# STM32F103-V1_0.net
KiCad netlist of a schematic drawn in Altium Designer
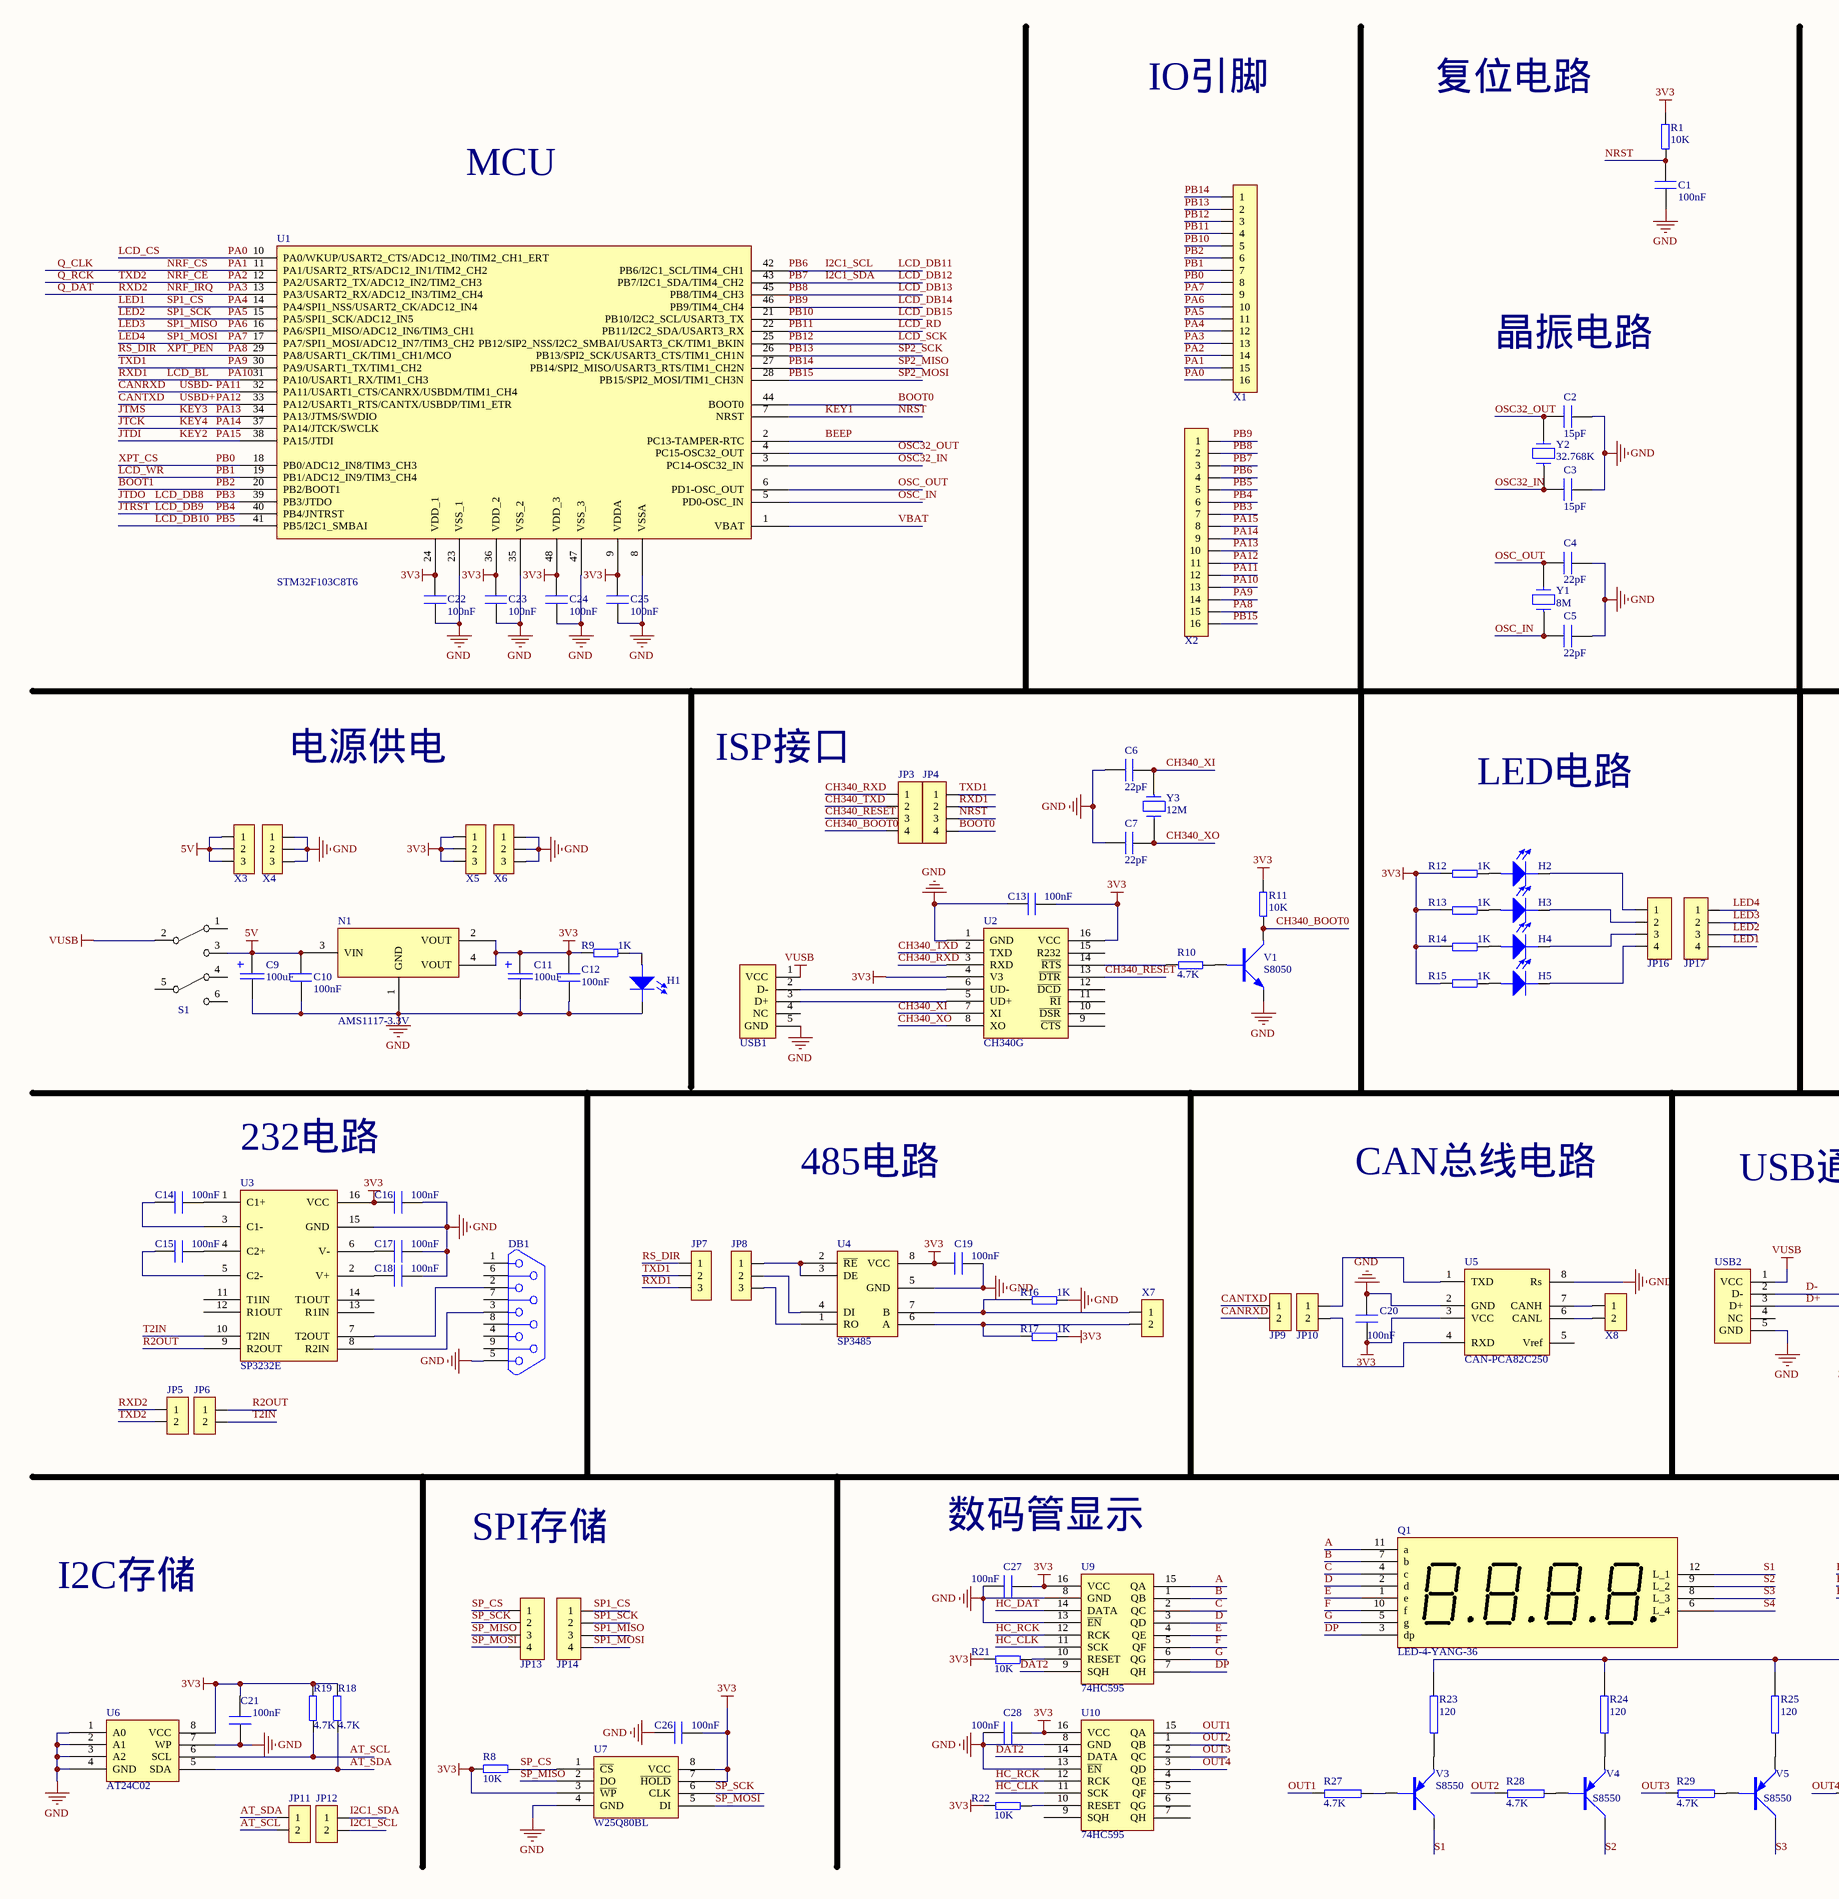
[diagram p0: STM32F103-V1.0.SchDoc, left]
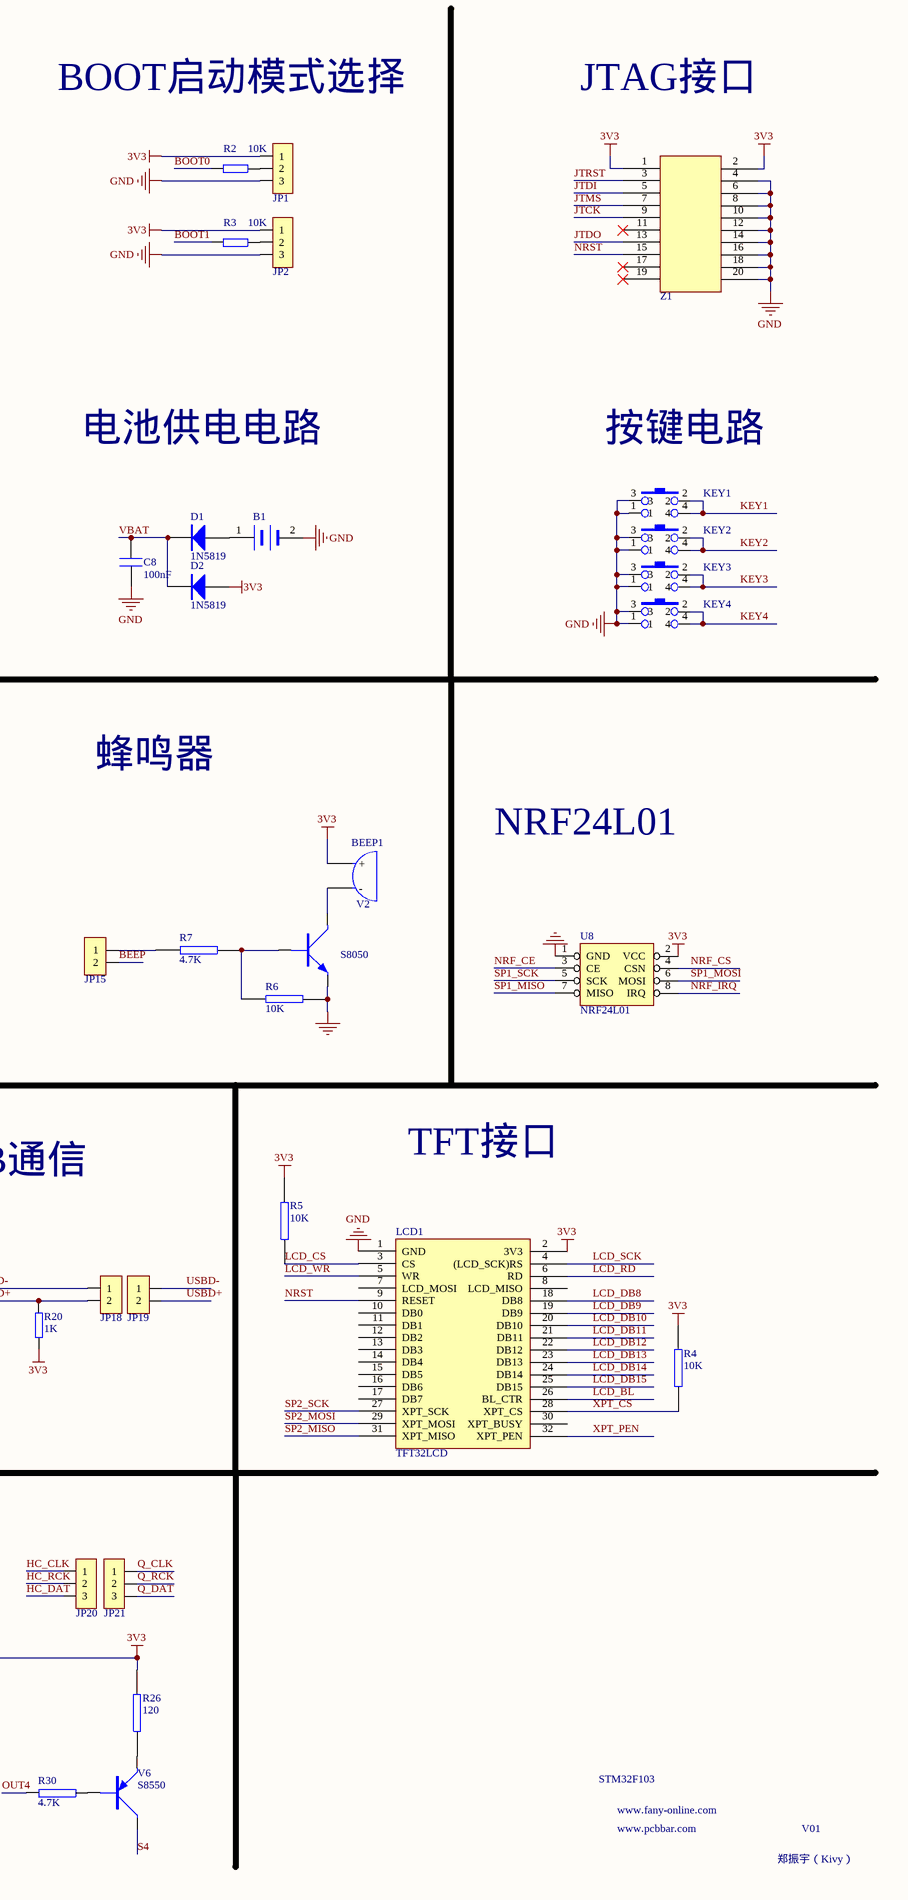
[diagram p1: STM32F103-V1.0.SchDoc, right]

(export (version "E")
  (design (tool "Eeschema 10.0.6"))
  (components
    (comp (ref "B1") (value "BATTERY") (footprint "CR1220") (libsource (lib "Liuzhx") (part "BATTERY")))
    (comp (ref "BEEP1") (value "BEEP") (footprint "SOT12-7.6") (libsource (lib "RationSTM32") (part "BEEP")))
    (comp (ref "C1")
      (value "100nF")
      (footprint "C0805")
      (description "Capacitor")
      (libsource (lib "Liuzhx") (part "普通贴片电容"))
    )
    (comp (ref "C2")
      (value "15pF")
      (footprint "C0805")
      (description "Capacitor")
      (libsource (lib "Liuzhx") (part "普通贴片电容"))
    )
    (comp (ref "C3")
      (value "15pF")
      (footprint "C0805")
      (description "Capacitor")
      (libsource (lib "Liuzhx") (part "普通贴片电容"))
    )
    (comp (ref "C4")
      (value "22pF")
      (footprint "C0805")
      (description "Capacitor")
      (libsource (lib "Liuzhx") (part "普通贴片电容"))
    )
    (comp (ref "C5")
      (value "22pF")
      (footprint "C0805")
      (description "Capacitor")
      (libsource (lib "Liuzhx") (part "普通贴片电容"))
    )
    (comp (ref "C6")
      (value "22pF")
      (footprint "C0805")
      (description "Capacitor")
      (libsource (lib "Liuzhx") (part "普通贴片电容"))
    )
    (comp (ref "C7")
      (value "22pF")
      (footprint "C0805")
      (description "Capacitor")
      (libsource (lib "Liuzhx") (part "普通贴片电容"))
    )
    (comp (ref "C8")
      (value "100nF")
      (footprint "C0805")
      (description "Capacitor")
      (libsource (lib "Liuzhx") (part "普通贴片电容"))
    )
    (comp (ref "C9") (value "100uF") (footprint "CAP5*5_4") (libsource (lib "Liuzhx") (part "极性电容器")))
    (comp (ref "C10")
      (value "100nF")
      (footprint "C0805")
      (description "Capacitor")
      (libsource (lib "Liuzhx") (part "普通贴片电容"))
    )
    (comp (ref "C11") (value "100uF") (footprint "CAP5*5_4") (libsource (lib "Liuzhx") (part "极性电容器")))
    (comp (ref "C12")
      (value "100nF")
      (footprint "C0805")
      (description "Capacitor")
      (libsource (lib "Liuzhx") (part "普通贴片电容"))
    )
    (comp (ref "C13")
      (value "100nF")
      (footprint "C0805")
      (description "Capacitor")
      (libsource (lib "Liuzhx") (part "普通贴片电容"))
    )
    (comp (ref "C14")
      (value "100nF")
      (footprint "C0805")
      (description "Capacitor")
      (libsource (lib "Liuzhx") (part "普通贴片电容"))
    )
    (comp (ref "C15")
      (value "100nF")
      (footprint "C0805")
      (description "Capacitor")
      (libsource (lib "Liuzhx") (part "普通贴片电容"))
    )
    (comp (ref "C16")
      (value "100nF")
      (footprint "C0805")
      (description "Capacitor")
      (libsource (lib "Liuzhx") (part "普通贴片电容"))
    )
    (comp (ref "C17")
      (value "100nF")
      (footprint "C0805")
      (description "Capacitor")
      (libsource (lib "Liuzhx") (part "普通贴片电容"))
    )
    (comp (ref "C18")
      (value "100nF")
      (footprint "C0805")
      (description "Capacitor")
      (libsource (lib "Liuzhx") (part "普通贴片电容"))
    )
    (comp (ref "C19")
      (value "100nF")
      (footprint "C0805")
      (description "Capacitor")
      (libsource (lib "Liuzhx") (part "普通贴片电容"))
    )
    (comp (ref "C20")
      (value "100nF")
      (footprint "C0805")
      (description "Capacitor")
      (libsource (lib "GKSSCH") (part "普通贴片电容"))
    )
    (comp (ref "C21")
      (value "100nF")
      (footprint "C0805")
      (description "Capacitor")
      (libsource (lib "Liuzhx") (part "普通贴片电容"))
    )
    (comp (ref "C22")
      (value "100nF")
      (footprint "C0805")
      (description "Capacitor")
      (libsource (lib "Liuzhx") (part "普通贴片电容"))
    )
    (comp (ref "C23")
      (value "100nF")
      (footprint "C0805")
      (description "Capacitor")
      (libsource (lib "Liuzhx") (part "普通贴片电容"))
    )
    (comp (ref "C24")
      (value "100nF")
      (footprint "C0805")
      (description "Capacitor")
      (libsource (lib "Liuzhx") (part "普通贴片电容"))
    )
    (comp (ref "C25")
      (value "100nF")
      (footprint "C0805")
      (description "Capacitor")
      (libsource (lib "Liuzhx") (part "普通贴片电容"))
    )
    (comp (ref "C26")
      (value "100nF")
      (footprint "C0805")
      (description "Capacitor")
      (libsource (lib "Liuzhx") (part "普通贴片电容"))
    )
    (comp (ref "C27")
      (value "100nF")
      (footprint "C0805")
      (description "Capacitor")
      (libsource (lib "Liuzhx") (part "普通贴片电容"))
    )
    (comp (ref "C28")
      (value "100nF")
      (footprint "C0805")
      (description "Capacitor")
      (libsource (lib "Liuzhx") (part "普通贴片电容"))
    )
    (comp (ref "D1")
      (value "1N5819")
      (footprint "1N4148-T")
      (description "Diode 1N series")
      (libsource (lib "Liuzhx") (part "贴片二极管"))
    )
    (comp (ref "D2")
      (value "1N5819")
      (footprint "1N4148-T")
      (description "Diode 1N series")
      (libsource (lib "Liuzhx") (part "贴片二极管"))
    )
    (comp (ref "DB1")
      (value "DB9M")
      (footprint "DB9-M")
      (description "母头")
      (libsource (lib "Liuzhx") (part "DB9M"))
    )
    (comp (ref "H1") (value "发光二极管") (footprint "LED1206") (libsource (lib "Liuzhx") (part "发光二极管")))
    (comp (ref "H2") (value "发光二极管") (footprint "LED1206") (libsource (lib "Liuzhx") (part "发光二极管")))
    (comp (ref "H3") (value "发光二极管") (footprint "LED1206") (libsource (lib "Liuzhx") (part "发光二极管")))
    (comp (ref "H4") (value "发光二极管") (footprint "LED1206") (libsource (lib "Liuzhx") (part "发光二极管")))
    (comp (ref "H5") (value "发光二极管") (footprint "LED1206") (libsource (lib "Liuzhx") (part "发光二极管")))
    (comp (ref "JP1")
      (value "JX3")
      (footprint "SIP3")
      (description "Connector")
      (libsource (lib "") (part "JX3_1"))
    )
    (comp (ref "JP2")
      (value "JX3")
      (footprint "SIP3")
      (description "Connector")
      (libsource (lib "") (part "JX3_1"))
    )
    (comp (ref "JP3")
      (value "JX4")
      (footprint "SIP4")
      (description "Connector")
      (libsource (lib "") (part "JX4_1"))
    )
    (comp (ref "JP4")
      (value "JX4")
      (footprint "SIP4")
      (description "Connector")
      (libsource (lib "Liuzhx") (part "JX4"))
    )
    (comp (ref "JP5")
      (value "JX2")
      (footprint "SIP2")
      (description "Connector")
      (libsource (lib "Liuzhx") (part "JX2"))
    )
    (comp (ref "JP6")
      (value "JX2")
      (footprint "SIP2")
      (description "Connector")
      (libsource (lib "") (part "JX2_1"))
    )
    (comp (ref "JP7")
      (value "JX3")
      (footprint "SIP3")
      (description "Connector")
      (libsource (lib "") (part "JX3_1"))
    )
    (comp (ref "JP8")
      (value "JX3")
      (footprint "SIP3")
      (description "Connector")
      (libsource (lib "Liuzhx") (part "JX3"))
    )
    (comp (ref "JP9")
      (value "JX2")
      (footprint "SIP2")
      (description "Connector")
      (libsource (lib "GKSSCH") (part "JX2"))
    )
    (comp (ref "JP10")
      (value "JX2")
      (footprint "SIP2")
      (description "Connector")
      (libsource (lib "") (part "JX2_1"))
    )
    (comp (ref "JP11")
      (value "JX2")
      (footprint "SIP2")
      (description "Connector")
      (libsource (lib "Liuzhx") (part "JX2"))
    )
    (comp (ref "JP12")
      (value "JX2")
      (footprint "SIP2")
      (description "Connector")
      (libsource (lib "") (part "JX2_1"))
    )
    (comp (ref "JP13")
      (value "JX4")
      (footprint "SIP4")
      (description "Connector")
      (libsource (lib "") (part "JX4_1"))
    )
    (comp (ref "JP14")
      (value "JX4")
      (footprint "SIP4")
      (description "Connector")
      (libsource (lib "Liuzhx") (part "JX4"))
    )
    (comp (ref "JP15")
      (value "JX2")
      (footprint "SIP2")
      (description "Connector")
      (libsource (lib "") (part "JX2_1"))
    )
    (comp (ref "JP16")
      (value "JX4")
      (footprint "SIP4")
      (description "Connector")
      (libsource (lib "") (part "JX4_1"))
    )
    (comp (ref "JP17")
      (value "JX4")
      (footprint "SIP4")
      (description "Connector")
      (libsource (lib "Liuzhx") (part "JX4"))
    )
    (comp (ref "JP18")
      (value "JX2")
      (footprint "SIP2")
      (description "Connector")
      (libsource (lib "Liuzhx") (part "JX2"))
    )
    (comp (ref "JP19")
      (value "JX2")
      (footprint "SIP2")
      (description "Connector")
      (libsource (lib "") (part "JX2_1"))
    )
    (comp (ref "JP20")
      (value "JX3")
      (footprint "SIP3")
      (description "Connector")
      (libsource (lib "") (part "JX3_1"))
    )
    (comp (ref "JP21")
      (value "JX3")
      (footprint "SIP3")
      (description "Connector")
      (libsource (lib "Liuzhx") (part "JX3"))
    )
    (comp (ref "KEY1") (value "SW-66B7") (footprint "SW-66") (libsource (lib "Liuzhx") (part "SW-66B7")))
    (comp (ref "KEY2") (value "SW-66B7") (footprint "SW-66") (libsource (lib "Liuzhx") (part "SW-66B7")))
    (comp (ref "KEY3") (value "SW-66B7") (footprint "SW-66") (libsource (lib "Liuzhx") (part "SW-66B7")))
    (comp (ref "KEY4") (value "SW-66B7") (footprint "SW-66") (libsource (lib "Liuzhx") (part "SW-66B7")))
    (comp (ref "LCD1") (value "TFT32LCD") (footprint "HEAD16×2") (libsource (lib "Liuzhx") (part "TFT32LCD")))
    (comp (ref "N1")
      (value "AMS1117-3.3V")
      (footprint "SOT223")
      (libsource (lib "Liuzhx") (part "AMS1117-3.3V"))
    )
    (comp (ref "Q1")
      (value "LED-4-YANG-36")
      (footprint "LED0.36-4")
      (libsource (lib "Liuzhx") (part "LED-4-YANG-36"))
    )
    (comp (ref "R1") (value "10K") (footprint "R0805") (libsource (lib "Liuzhx") (part "普通贴片电阻")))
    (comp (ref "R2") (value "10K") (footprint "R0805") (libsource (lib "Liuzhx") (part "普通贴片电阻")))
    (comp (ref "R3") (value "10K") (footprint "R0805") (libsource (lib "Liuzhx") (part "普通贴片电阻")))
    (comp (ref "R4") (value "10K") (footprint "R0805") (libsource (lib "RationSTM32") (part "RES")))
    (comp (ref "R5") (value "10K") (footprint "R0805") (libsource (lib "RationSTM32") (part "RES")))
    (comp (ref "R6") (value "10K") (footprint "R0805") (libsource (lib "RationSTM32") (part "RES")))
    (comp (ref "R7") (value "4.7K") (footprint "R0805") (libsource (lib "RationSTM32") (part "RES")))
    (comp (ref "R8") (value "10K") (footprint "R0805") (libsource (lib "Liuzhx") (part "普通贴片电阻")))
    (comp (ref "R9") (value "1K") (footprint "R0805") (libsource (lib "Liuzhx") (part "普通贴片电阻")))
    (comp (ref "R10") (value "4.7K") (footprint "R0805") (libsource (lib "Liuzhx") (part "普通贴片电阻")))
    (comp (ref "R11") (value "10K") (footprint "R0805") (libsource (lib "Liuzhx") (part "普通贴片电阻")))
    (comp (ref "R12") (value "1K") (footprint "R0805") (libsource (lib "Liuzhx") (part "普通贴片电阻")))
    (comp (ref "R13") (value "1K") (footprint "R0805") (libsource (lib "Liuzhx") (part "普通贴片电阻")))
    (comp (ref "R14") (value "1K") (footprint "R0805") (libsource (lib "Liuzhx") (part "普通贴片电阻")))
    (comp (ref "R15") (value "1K") (footprint "R0805") (libsource (lib "Liuzhx") (part "普通贴片电阻")))
    (comp (ref "R16") (value "1K") (footprint "R0805") (libsource (lib "Liuzhx") (part "普通贴片电阻")))
    (comp (ref "R17") (value "1K") (footprint "R0805") (libsource (lib "Liuzhx") (part "普通贴片电阻")))
    (comp (ref "R18") (value "4.7K") (footprint "R0805") (libsource (lib "Liuzhx") (part "普通贴片电阻")))
    (comp (ref "R19") (value "4.7K") (footprint "R0805") (libsource (lib "Liuzhx") (part "普通贴片电阻")))
    (comp (ref "R20") (value "1K") (footprint "R0805") (libsource (lib "Liuzhx") (part "普通贴片电阻")))
    (comp (ref "R21") (value "10K") (footprint "R0805") (libsource (lib "Liuzhx") (part "普通贴片电阻")))
    (comp (ref "R22") (value "10K") (footprint "R0805") (libsource (lib "Liuzhx") (part "普通贴片电阻")))
    (comp (ref "R23") (value "120") (footprint "R0805") (libsource (lib "STM32F103-V1.0") (part "RES")))
    (comp (ref "R24") (value "120") (footprint "R0805") (libsource (lib "STM32F103-V1.0") (part "RES")))
    (comp (ref "R25") (value "120") (footprint "R0805") (libsource (lib "STM32F103-V1.0") (part "RES")))
    (comp (ref "R26") (value "120") (footprint "R0805") (libsource (lib "STM32F103-V1.0") (part "RES")))
    (comp (ref "R27") (value "4.7K") (footprint "R0805") (libsource (lib "STM32F103-V1.0") (part "RES2")))
    (comp (ref "R28") (value "4.7K") (footprint "R0805") (libsource (lib "STM32F103-V1.0") (part "RES2")))
    (comp (ref "R29") (value "4.7K") (footprint "R0805") (libsource (lib "STM32F103-V1.0") (part "RES2")))
    (comp (ref "R30") (value "4.7K") (footprint "R0805") (libsource (lib "STM32F103-V1.0") (part "RES2")))
    (comp (ref "S1") (value "SWITCH-6") (footprint "SW-AJ") (libsource (lib "Liuzhx") (part "SWITCH-6")))
    (comp (ref "U1")
      (value "STM32F103C8T6")
      (footprint "LQFP48")
      (libsource (lib "STM32F103-V1.0") (part "STM32F103C8T6"))
    )
    (comp (ref "U2") (value "CH340G") (footprint "SOIC16") (libsource (lib "Liuzhx") (part "CH340G")))
    (comp (ref "U3")
      (value "SP3232E")
      (footprint "SOIC16")
      (description "SP3232EEN-L/TR;SOIC-39MM")
      (libsource (lib "Liuzhx") (part "SP3232E"))
    )
    (comp (ref "U4") (value "SP3485") (footprint "SO-8") (libsource (lib "Liuzhx") (part "MAX3082")))
    (comp (ref "U5")
      (value "CAN-PCA82C250")
      (footprint "SO-8")
      (libsource (lib "GKSSCH") (part "CAN-PCA82C250"))
    )
    (comp (ref "U6") (value "AT24C02") (footprint "SO-8") (libsource (lib "Liuzhx") (part "AT24C02")))
    (comp (ref "U7") (value "W25Q80BL") (footprint "W25Q-SO8") (libsource (lib "Liuzhx") (part "W25Q80BL")))
    (comp (ref "U8") (value "NRF24L01") (footprint "NRF24L01") (libsource (lib "Liuzhx") (part "NRF24L01")))
    (comp (ref "U9")
      (value "74HC595")
      (footprint "SO-16")
      (description "串入并出移位寄存器")
      (libsource (lib "Liuzhx") (part "74HC595"))
    )
    (comp (ref "U10")
      (value "74HC595")
      (footprint "SO-16")
      (description "串入并出移位寄存器")
      (libsource (lib "Liuzhx") (part "74HC595"))
    )
    (comp (ref "USB1")
      (value "MicroUSB")
      (footprint "MicroUSB1")
      (description "母头")
      (libsource (lib "Liuzhx") (part "MicroUSB"))
    )
    (comp (ref "USB2")
      (value "MicroUSB")
      (footprint "MicroUSB1")
      (description "母头")
      (libsource (lib "Liuzhx") (part "MicroUSB"))
    )
    (comp (ref "V1")
      (value "S8050")
      (footprint "SOT23-C1")
      (description "V")
      (libsource (lib "Liuzhx") (part "NPN三极管"))
    )
    (comp (ref "V2")
      (value "S8050")
      (footprint "SOT23-C1")
      (description "V")
      (libsource (lib "Liuzhx") (part "NPN三极管"))
    )
    (comp (ref "V3")
      (value "S8550")
      (footprint "SOT23-C1")
      (description "V")
      (libsource (lib "*") (part "PNP三极管"))
    )
    (comp (ref "V4")
      (value "S8550")
      (footprint "SOT23-C1")
      (description "V")
      (libsource (lib "*") (part "PNP三极管"))
    )
    (comp (ref "V5")
      (value "S8550")
      (footprint "SOT23-C1")
      (description "V")
      (libsource (lib "*") (part "PNP三极管"))
    )
    (comp (ref "V6")
      (value "S8550")
      (footprint "SOT23-C1")
      (description "V")
      (libsource (lib "*") (part "PNP三极管"))
    )
    (comp (ref "X1") (value "JX16") (footprint "SIP16") (libsource (lib "Liuzhx") (part "JX16")))
    (comp (ref "X2") (value "JX16") (footprint "SIP16") (libsource (lib "") (part "JX16_1")))
    (comp (ref "X3")
      (value "JX3")
      (footprint "SIP3")
      (description "Connector")
      (libsource (lib "") (part "JX3_1"))
    )
    (comp (ref "X4")
      (value "JX3")
      (footprint "SIP3")
      (description "Connector")
      (libsource (lib "Liuzhx") (part "JX3"))
    )
    (comp (ref "X5")
      (value "JX3")
      (footprint "SIP3")
      (description "Connector")
      (libsource (lib "") (part "JX3_1"))
    )
    (comp (ref "X6")
      (value "JX3")
      (footprint "SIP3")
      (description "Connector")
      (libsource (lib "Liuzhx") (part "JX3"))
    )
    (comp (ref "X7")
      (value "JX2")
      (footprint "WJ128-5.0-2P")
      (description "Connector")
      (libsource (lib "Liuzhx") (part "JX2"))
    )
    (comp (ref "X8")
      (value "JX2")
      (footprint "WJ128-5.0-2P")
      (description "Connector")
      (libsource (lib "GKSSCH") (part "JX2"))
    )
    (comp (ref "Y1")
      (value "8M")
      (footprint "JZ-AX")
      (description "Crystal")
      (libsource (lib "Liuzhx") (part "CRYSTAL"))
    )
    (comp (ref "Y2")
      (value "32.768K")
      (footprint "FC135")
      (description "Crystal")
      (libsource (lib "Liuzhx") (part "CRYSTAL"))
    )
    (comp (ref "Y3")
      (value "12M")
      (footprint "JZ-AX")
      (description "Crystal")
      (libsource (lib "Liuzhx") (part "CRYSTAL"))
    )
    (comp (ref "Z1") (value "HEADER 10X2") (footprint "JTAG") (libsource (lib "STM32") (part "HEADER 10X2")))
  )
  (nets
    (net (code "1") (name "/A") (class "Default")
      (node (ref "Q1") (pin "11") (pinfunction "a_11") (pintype "passive"))
      (node (ref "U9") (pin "15") (pinfunction "QA_15") (pintype "passive"))
    )
    (net (code "2") (name "/AT_SCL") (class "Default")
      (node (ref "JP11") (pin "2") (pinfunction "2_2") (pintype "passive"))
      (node (ref "R19") (pin "1") (pinfunction "1_1") (pintype "passive"))
      (node (ref "U6") (pin "6") (pinfunction "SCL_6") (pintype "passive"))
    )
    (net (code "3") (name "/AT_SDA") (class "Default")
      (node (ref "JP11") (pin "1") (pinfunction "1_1") (pintype "passive"))
      (node (ref "R18") (pin "1") (pinfunction "1_1") (pintype "passive"))
      (node (ref "U6") (pin "5") (pinfunction "SDA_5") (pintype "passive"))
    )
    (net (code "4") (name "/B") (class "Default")
      (node (ref "Q1") (pin "7") (pinfunction "b_7") (pintype "passive"))
      (node (ref "U9") (pin "1") (pinfunction "QB_1") (pintype "passive"))
    )
    (net (code "5") (name "/BEEP") (class "Default")
      (node (ref "JP15") (pin "2") (pinfunction "2_2") (pintype "passive"))
      (node (ref "U1") (pin "2") (pinfunction "PC13-TAMPER-RTC_2") (pintype "passive"))
    )
    (net (code "6") (name "/BOOT0") (class "Default")
      (node (ref "JP4") (pin "4") (pinfunction "4_4") (pintype "passive"))
      (node (ref "R2") (pin "1") (pinfunction "1_1") (pintype "passive"))
      (node (ref "U1") (pin "44") (pinfunction "BOOT0_44") (pintype "passive"))
    )
    (net (code "7") (name "/BOOT1") (class "Default")
      (node (ref "R3") (pin "1") (pinfunction "1_1") (pintype "passive"))
      (node (ref "U1") (pin "20") (pinfunction "PB2/BOOT1_20") (pintype "passive"))
      (node (ref "X1") (pin "6") (pinfunction "6_6") (pintype "passive"))
    )
    (net (code "8") (name "/C") (class "Default")
      (node (ref "Q1") (pin "4") (pinfunction "c_4") (pintype "passive"))
      (node (ref "U9") (pin "2") (pinfunction "QC_2") (pintype "passive"))
    )
    (net (code "9") (name "/CANRXD") (class "Default")
      (node (ref "JP19") (pin "1") (pinfunction "1_1") (pintype "passive"))
      (node (ref "JP9") (pin "2") (pinfunction "2_2") (pintype "passive"))
      (node (ref "U1") (pin "32") (pinfunction "PA11/USART1_CTS/CANRX/USBDM/TIM1_CH4_32") (pintype "passive"))
      (node (ref "X2") (pin "12") (pinfunction "12_12") (pintype "passive"))
    )
    (net (code "10") (name "/CANTXD") (class "Default")
      (node (ref "JP19") (pin "2") (pinfunction "2_2") (pintype "passive"))
      (node (ref "JP9") (pin "1") (pinfunction "1_1") (pintype "passive"))
      (node (ref "U1") (pin "33") (pinfunction "PA12/USART1_RTS/CANTX/USBDP/TIM1_ETR_33") (pintype "passive"))
      (node (ref "X2") (pin "11") (pinfunction "11_11") (pintype "passive"))
    )
    (net (code "11") (name "/CH340_BOOT0") (class "Default")
      (node (ref "JP3") (pin "4") (pinfunction "4_4") (pintype "passive"))
      (node (ref "R11") (pin "1") (pinfunction "1_1") (pintype "passive"))
      (node (ref "V1") (pin "C") (pinfunction "C_C") (pintype "passive"))
    )
    (net (code "12") (name "/CH340_RESET") (class "Default")
      (node (ref "JP3") (pin "3") (pinfunction "3_3") (pintype "passive"))
      (node (ref "U2") (pin "13") (pinfunction "~{DTR}_13") (pintype "passive"))
    )
    (net (code "13") (name "/CH340_RXD") (class "Default")
      (node (ref "JP3") (pin "1") (pinfunction "1_1") (pintype "passive"))
      (node (ref "U2") (pin "3") (pinfunction "RXD_3") (pintype "passive"))
    )
    (net (code "14") (name "/CH340_TXD") (class "Default")
      (node (ref "JP3") (pin "2") (pinfunction "2_2") (pintype "passive"))
      (node (ref "U2") (pin "2") (pinfunction "TXD_2") (pintype "passive"))
    )
    (net (code "15") (name "/CH340_XI") (class "Default")
      (node (ref "C6") (pin "2") (pinfunction "2_2") (pintype "passive"))
      (node (ref "U2") (pin "7") (pinfunction "XI_7") (pintype "passive"))
      (node (ref "Y3") (pin "1") (pinfunction "1_1") (pintype "passive"))
    )
    (net (code "16") (name "/CH340_XO") (class "Default")
      (node (ref "C7") (pin "2") (pinfunction "2_2") (pintype "passive"))
      (node (ref "U2") (pin "8") (pinfunction "XO_8") (pintype "passive"))
      (node (ref "Y3") (pin "2") (pinfunction "2_2") (pintype "passive"))
    )
    (net (code "17") (name "/D") (class "Default")
      (node (ref "Q1") (pin "2") (pinfunction "d_2") (pintype "passive"))
      (node (ref "U9") (pin "3") (pinfunction "QD_3") (pintype "passive"))
    )
    (net (code "18") (name "/D+") (class "Default")
      (node (ref "JP18") (pin "2") (pinfunction "2_2") (pintype "passive"))
      (node (ref "R20") (pin "1") (pinfunction "1_1") (pintype "passive"))
      (node (ref "USB2") (pin "3") (pinfunction "D+_3") (pintype "passive"))
    )
    (net (code "19") (name "/D-") (class "Default")
      (node (ref "JP18") (pin "1") (pinfunction "1_1") (pintype "passive"))
      (node (ref "USB2") (pin "2") (pinfunction "D-_2") (pintype "passive"))
    )
    (net (code "20") (name "/DAT2") (class "Default")
      (node (ref "U10") (pin "14") (pinfunction "DATA_14") (pintype "passive"))
      (node (ref "U9") (pin "9") (pinfunction "SQH_9") (pintype "passive"))
    )
    (net (code "21") (name "/DP") (class "Default")
      (node (ref "Q1") (pin "3") (pinfunction "dp_3") (pintype "passive"))
      (node (ref "U9") (pin "7") (pinfunction "QH_7") (pintype "passive"))
    )
    (net (code "22") (name "/E") (class "Default")
      (node (ref "Q1") (pin "1") (pinfunction "e_1") (pintype "passive"))
      (node (ref "U9") (pin "4") (pinfunction "QE_4") (pintype "passive"))
    )
    (net (code "23") (name "/F") (class "Default")
      (node (ref "Q1") (pin "10") (pinfunction "f_10") (pintype "passive"))
      (node (ref "U9") (pin "5") (pinfunction "QF_5") (pintype "passive"))
    )
    (net (code "24") (name "/G") (class "Default")
      (node (ref "Q1") (pin "5") (pinfunction "g_5") (pintype "passive"))
      (node (ref "U9") (pin "6") (pinfunction "QG_6") (pintype "passive"))
    )
    (net (code "25") (name "/HC_CLK") (class "Default")
      (node (ref "JP20") (pin "1") (pinfunction "1_1") (pintype "passive"))
      (node (ref "U10") (pin "11") (pinfunction "SCK_11") (pintype "passive"))
      (node (ref "U9") (pin "11") (pinfunction "SCK_11") (pintype "passive"))
    )
    (net (code "26") (name "/HC_DAT") (class "Default")
      (node (ref "JP20") (pin "3") (pinfunction "3_3") (pintype "passive"))
      (node (ref "U9") (pin "14") (pinfunction "DATA_14") (pintype "passive"))
    )
    (net (code "27") (name "/HC_RCK") (class "Default")
      (node (ref "JP20") (pin "2") (pinfunction "2_2") (pintype "passive"))
      (node (ref "U10") (pin "12") (pinfunction "RCK_12") (pintype "passive"))
      (node (ref "U9") (pin "12") (pinfunction "RCK_12") (pintype "passive"))
    )
    (net (code "28") (name "/I2C1_SCL") (class "Default")
      (node (ref "JP12") (pin "2") (pinfunction "2_2") (pintype "passive"))
      (node (ref "LCD1") (pin "21") (pinfunction "DB11_21") (pintype "passive"))
      (node (ref "U1") (pin "42") (pinfunction "PB6/I2C1_SCL/TIM4_CH1_42") (pintype "passive"))
      (node (ref "X2") (pin "4") (pinfunction "4_4") (pintype "passive"))
    )
    (net (code "29") (name "/I2C1_SDA") (class "Default")
      (node (ref "JP12") (pin "1") (pinfunction "1_1") (pintype "passive"))
      (node (ref "LCD1") (pin "22") (pinfunction "DB12_22") (pintype "passive"))
      (node (ref "U1") (pin "43") (pinfunction "PB7/I2C1_SDA/TIM4_CH2_43") (pintype "passive"))
      (node (ref "X2") (pin "3") (pinfunction "3_3") (pintype "passive"))
    )
    (net (code "30") (name "/JTCK") (class "Default")
      (node (ref "KEY4") (pin "2") (pinfunction "2_2") (pintype "passive"))
      (node (ref "KEY4") (pin "4") (pinfunction "4_4") (pintype "passive"))
      (node (ref "U1") (pin "37") (pinfunction "PA14/JTCK/SWCLK_37") (pintype "passive"))
      (node (ref "X2") (pin "9") (pinfunction "9_9") (pintype "passive"))
      (node (ref "Z1") (pin "9") (pinfunction "9_9") (pintype "passive"))
    )
    (net (code "31") (name "/JTDI") (class "Default")
      (node (ref "KEY2") (pin "2") (pinfunction "2_2") (pintype "passive"))
      (node (ref "KEY2") (pin "4") (pinfunction "4_4") (pintype "passive"))
      (node (ref "U1") (pin "38") (pinfunction "PA15/JTDI_38") (pintype "passive"))
      (node (ref "X2") (pin "8") (pinfunction "8_8") (pintype "passive"))
      (node (ref "Z1") (pin "5") (pinfunction "5_5") (pintype "passive"))
    )
    (net (code "32") (name "/JTDO") (class "Default")
      (node (ref "LCD1") (pin "18") (pinfunction "DB8_18") (pintype "passive"))
      (node (ref "U1") (pin "39") (pinfunction "PB3/JTDO_39") (pintype "passive"))
      (node (ref "X2") (pin "7") (pinfunction "7_7") (pintype "passive"))
      (node (ref "Z1") (pin "13") (pinfunction "13_13") (pintype "passive"))
    )
    (net (code "33") (name "/JTMS") (class "Default")
      (node (ref "KEY3") (pin "2") (pinfunction "2_2") (pintype "passive"))
      (node (ref "KEY3") (pin "4") (pinfunction "4_4") (pintype "passive"))
      (node (ref "U1") (pin "34") (pinfunction "PA13/JTMS/SWDIO_34") (pintype "passive"))
      (node (ref "X2") (pin "10") (pinfunction "10_10") (pintype "passive"))
      (node (ref "Z1") (pin "7") (pinfunction "7_7") (pintype "passive"))
    )
    (net (code "34") (name "/JTRST") (class "Default")
      (node (ref "LCD1") (pin "19") (pinfunction "DB9_19") (pintype "passive"))
      (node (ref "U1") (pin "40") (pinfunction "PB4/JNTRST_40") (pintype "passive"))
      (node (ref "X2") (pin "6") (pinfunction "6_6") (pintype "passive"))
      (node (ref "Z1") (pin "3") (pinfunction "3_3") (pintype "passive"))
    )
    (net (code "35") (name "/KEY1") (class "Default")
      (node (ref "C1") (pin "2") (pinfunction "2_2") (pintype "passive"))
      (node (ref "JP4") (pin "3") (pinfunction "3_3") (pintype "passive"))
      (node (ref "KEY1") (pin "2") (pinfunction "2_2") (pintype "passive"))
      (node (ref "KEY1") (pin "4") (pinfunction "4_4") (pintype "passive"))
      (node (ref "LCD1") (pin "9") (pinfunction "RESET_9") (pintype "passive"))
      (node (ref "R1") (pin "1") (pinfunction "1_1") (pintype "passive"))
      (node (ref "U1") (pin "7") (pinfunction "NRST_7") (pintype "passive"))
      (node (ref "Z1") (pin "15") (pinfunction "15_15") (pintype "passive"))
    )
    (net (code "36") (name "/LCD_BL") (class "Default")
      (node (ref "JP4") (pin "2") (pinfunction "2_2") (pintype "passive"))
      (node (ref "JP7") (pin "3") (pinfunction "3_3") (pintype "passive"))
      (node (ref "LCD1") (pin "26") (pinfunction "BL_CTR_26") (pintype "passive"))
      (node (ref "U1") (pin "31") (pinfunction "PA10/USART1_RX/TIM1_CH3_31") (pintype "passive"))
      (node (ref "X2") (pin "13") (pinfunction "13_13") (pintype "passive"))
    )
    (net (code "37") (name "/LCD_CS") (class "Default")
      (node (ref "LCD1") (pin "3") (pinfunction "CS_3") (pintype "passive"))
      (node (ref "R5") (pin "1") (pinfunction "1_1") (pintype "passive"))
      (node (ref "U1") (pin "10") (pinfunction "PA0/WKUP/USART2_CTS/ADC12_IN0/TIM2_CH1_ERT_10") (pintype "passive"))
      (node (ref "X1") (pin "16") (pinfunction "16_16") (pintype "passive"))
    )
    (net (code "38") (name "/LCD_DB10") (class "Default")
      (node (ref "LCD1") (pin "20") (pinfunction "DB10_20") (pintype "passive"))
      (node (ref "U1") (pin "41") (pinfunction "PB5/I2C1_SMBAI_41") (pintype "passive"))
      (node (ref "X2") (pin "5") (pinfunction "5_5") (pintype "passive"))
    )
    (net (code "39") (name "/LCD_DB13") (class "Default")
      (node (ref "LCD1") (pin "23") (pinfunction "DB13_23") (pintype "passive"))
      (node (ref "U1") (pin "45") (pinfunction "PB8/TIM4_CH3_45") (pintype "passive"))
      (node (ref "X2") (pin "2") (pinfunction "2_2") (pintype "passive"))
    )
    (net (code "40") (name "/LCD_DB14") (class "Default")
      (node (ref "LCD1") (pin "24") (pinfunction "DB14_24") (pintype "passive"))
      (node (ref "U1") (pin "46") (pinfunction "PB9/TIM4_CH4_46") (pintype "passive"))
      (node (ref "X2") (pin "1") (pinfunction "1_1") (pintype "passive"))
    )
    (net (code "41") (name "/LCD_DB15") (class "Default")
      (node (ref "LCD1") (pin "25") (pinfunction "DB15_25") (pintype "passive"))
      (node (ref "U1") (pin "21") (pinfunction "PB10/I2C2_SCL/USART3_TX_21") (pintype "passive"))
      (node (ref "X1") (pin "5") (pinfunction "5_5") (pintype "passive"))
    )
    (net (code "42") (name "/LCD_RD") (class "Default")
      (node (ref "LCD1") (pin "6") (pinfunction "RD_6") (pintype "passive"))
      (node (ref "U1") (pin "22") (pinfunction "PB11/I2C2_SDA/USART3_RX_22") (pintype "passive"))
      (node (ref "X1") (pin "4") (pinfunction "4_4") (pintype "passive"))
    )
    (net (code "43") (name "/LCD_SCK") (class "Default")
      (node (ref "LCD1") (pin "4") (pinfunction "(LCD_SCK)RS_4") (pintype "passive"))
      (node (ref "U1") (pin "25") (pinfunction "PB12/SIP2_NSS/I2C2_SMBAI/USART3_CK/TIM1_BKIN_25") (pintype "passive"))
      (node (ref "X1") (pin "3") (pinfunction "3_3") (pintype "passive"))
    )
    (net (code "44") (name "/LCD_WR") (class "Default")
      (node (ref "LCD1") (pin "5") (pinfunction "WR_5") (pintype "passive"))
      (node (ref "U1") (pin "19") (pinfunction "PB1/ADC12_IN9/TIM3_CH4_19") (pintype "passive"))
      (node (ref "X1") (pin "7") (pinfunction "7_7") (pintype "passive"))
    )
    (net (code "45") (name "/LED1") (class "Default")
      (node (ref "JP14") (pin "1") (pinfunction "1_1") (pintype "passive"))
      (node (ref "JP17") (pin "4") (pinfunction "4_4") (pintype "passive"))
      (node (ref "U1") (pin "14") (pinfunction "PA4/SPI1_NSS/USART2_CK/ADC12_IN4_14") (pintype "passive"))
      (node (ref "X1") (pin "12") (pinfunction "12_12") (pintype "passive"))
    )
    (net (code "46") (name "/LED2") (class "Default")
      (node (ref "JP14") (pin "2") (pinfunction "2_2") (pintype "passive"))
      (node (ref "JP17") (pin "3") (pinfunction "3_3") (pintype "passive"))
      (node (ref "U1") (pin "15") (pinfunction "PA5/SPI1_SCK/ADC12_IN5_15") (pintype "passive"))
      (node (ref "U8") (pin "5") (pinfunction "SCK_5") (pintype "passive"))
      (node (ref "X1") (pin "11") (pinfunction "11_11") (pintype "passive"))
    )
    (net (code "47") (name "/LED3") (class "Default")
      (node (ref "JP14") (pin "3") (pinfunction "3_3") (pintype "passive"))
      (node (ref "JP17") (pin "2") (pinfunction "2_2") (pintype "passive"))
      (node (ref "U1") (pin "16") (pinfunction "PA6/SPI1_MISO/ADC12_IN6/TIM3_CH1_16") (pintype "passive"))
      (node (ref "U8") (pin "7") (pinfunction "MISO_7") (pintype "passive"))
      (node (ref "X1") (pin "10") (pinfunction "10_10") (pintype "passive"))
    )
    (net (code "48") (name "/LED4") (class "Default")
      (node (ref "JP14") (pin "4") (pinfunction "4_4") (pintype "passive"))
      (node (ref "JP17") (pin "1") (pinfunction "1_1") (pintype "passive"))
      (node (ref "U1") (pin "17") (pinfunction "PA7/SPI1_MOSI/ADC12_IN7/TIM3_CH2_17") (pintype "passive"))
      (node (ref "U8") (pin "6") (pinfunction "MOSI_6") (pintype "passive"))
      (node (ref "X1") (pin "9") (pinfunction "9_9") (pintype "passive"))
    )
    (net (code "49") (name "/NRF_CE") (class "Default")
      (node (ref "JP21") (pin "2") (pinfunction "2_2") (pintype "passive"))
      (node (ref "JP5") (pin "2") (pinfunction "2_2") (pintype "passive"))
      (node (ref "U1") (pin "12") (pinfunction "PA2/USART2_TX/ADC12_IN2/TIM2_CH3_12") (pintype "passive"))
      (node (ref "U8") (pin "3") (pinfunction "CE_3") (pintype "passive"))
      (node (ref "X1") (pin "14") (pinfunction "14_14") (pintype "passive"))
    )
    (net (code "50") (name "/NRF_CS") (class "Default")
      (node (ref "JP21") (pin "1") (pinfunction "1_1") (pintype "passive"))
      (node (ref "U1") (pin "11") (pinfunction "PA1/USART2_RTS/ADC12_IN1/TIM2_CH2_11") (pintype "passive"))
      (node (ref "U8") (pin "4") (pinfunction "CSN_4") (pintype "passive"))
      (node (ref "X1") (pin "15") (pinfunction "15_15") (pintype "passive"))
    )
    (net (code "51") (name "/NRF_IRQ") (class "Default")
      (node (ref "JP21") (pin "3") (pinfunction "3_3") (pintype "passive"))
      (node (ref "JP5") (pin "1") (pinfunction "1_1") (pintype "passive"))
      (node (ref "U1") (pin "13") (pinfunction "PA3/USART2_RX/ADC12_IN3/TIM2_CH4_13") (pintype "passive"))
      (node (ref "U8") (pin "8") (pinfunction "IRQ_8") (pintype "passive"))
      (node (ref "X1") (pin "13") (pinfunction "13_13") (pintype "passive"))
    )
    (net (code "52") (name "/OSC32_IN") (class "Default")
      (node (ref "C3") (pin "1") (pinfunction "1_1") (pintype "passive"))
      (node (ref "U1") (pin "3") (pinfunction "PC14-OSC32_IN_3") (pintype "passive"))
      (node (ref "Y2") (pin "1") (pinfunction "1_1") (pintype "passive"))
    )
    (net (code "53") (name "/OSC32_OUT") (class "Default")
      (node (ref "C2") (pin "1") (pinfunction "1_1") (pintype "passive"))
      (node (ref "U1") (pin "4") (pinfunction "PC15-OSC32_OUT_4") (pintype "passive"))
      (node (ref "Y2") (pin "2") (pinfunction "2_2") (pintype "passive"))
    )
    (net (code "54") (name "/OSC_IN") (class "Default")
      (node (ref "C5") (pin "1") (pinfunction "1_1") (pintype "passive"))
      (node (ref "U1") (pin "5") (pinfunction "PD0-OSC_IN_5") (pintype "passive"))
      (node (ref "Y1") (pin "1") (pinfunction "1_1") (pintype "passive"))
    )
    (net (code "55") (name "/OSC_OUT") (class "Default")
      (node (ref "C4") (pin "1") (pinfunction "1_1") (pintype "passive"))
      (node (ref "U1") (pin "6") (pinfunction "PD1-OSC_OUT_6") (pintype "passive"))
      (node (ref "Y1") (pin "2") (pinfunction "2_2") (pintype "passive"))
    )
    (net (code "56") (name "/OUT1") (class "Default")
      (node (ref "R27") (pin "1") (pintype "passive"))
      (node (ref "U10") (pin "15") (pinfunction "QA_15") (pintype "passive"))
    )
    (net (code "57") (name "/OUT2") (class "Default")
      (node (ref "R28") (pin "1") (pintype "passive"))
      (node (ref "U10") (pin "1") (pinfunction "QB_1") (pintype "passive"))
    )
    (net (code "58") (name "/OUT3") (class "Default")
      (node (ref "R29") (pin "1") (pintype "passive"))
      (node (ref "U10") (pin "2") (pinfunction "QC_2") (pintype "passive"))
    )
    (net (code "59") (name "/OUT4") (class "Default")
      (node (ref "R30") (pin "1") (pintype "passive"))
      (node (ref "U10") (pin "3") (pinfunction "QD_3") (pintype "passive"))
    )
    (net (code "60") (name "/PA8") (class "Default")
      (node (ref "JP7") (pin "1") (pinfunction "1_1") (pintype "passive"))
      (node (ref "LCD1") (pin "32") (pinfunction "XPT_PEN_32") (pintype "passive"))
      (node (ref "U1") (pin "29") (pinfunction "PA8/USART1_CK/TIM1_CH1/MCO_29") (pintype "passive"))
      (node (ref "X2") (pin "15") (pinfunction "15_15") (pintype "passive"))
    )
    (net (code "61") (name "/PA9") (class "Default")
      (node (ref "JP4") (pin "1") (pinfunction "1_1") (pintype "passive"))
      (node (ref "JP7") (pin "2") (pinfunction "2_2") (pintype "passive"))
      (node (ref "U1") (pin "30") (pinfunction "PA9/USART1_TX/TIM1_CH2_30") (pintype "passive"))
      (node (ref "X2") (pin "14") (pinfunction "14_14") (pintype "passive"))
    )
    (net (code "62") (name "/PB0") (class "Default")
      (node (ref "LCD1") (pin "28") (pinfunction "XPT_CS_28") (pintype "passive"))
      (node (ref "R4") (pin "2") (pinfunction "2_2") (pintype "passive"))
      (node (ref "U1") (pin "18") (pinfunction "PB0/ADC12_IN8/TIM3_CH3_18") (pintype "passive"))
      (node (ref "X1") (pin "8") (pinfunction "8_8") (pintype "passive"))
    )
    (net (code "63") (name "/PB13") (class "Default")
      (node (ref "LCD1") (pin "27") (pinfunction "XPT_SCK_27") (pintype "passive"))
      (node (ref "U1") (pin "26") (pinfunction "PB13/SPI2_SCK/USART3_CTS/TIM1_CH1N_26") (pintype "passive"))
      (node (ref "X1") (pin "2") (pinfunction "2_2") (pintype "passive"))
    )
    (net (code "64") (name "/PB14") (class "Default")
      (node (ref "LCD1") (pin "31") (pinfunction "XPT_MISO_31") (pintype "passive"))
      (node (ref "U1") (pin "27") (pinfunction "PB14/SPI2_MISO/USART3_RTS/TIM1_CH2N_27") (pintype "passive"))
      (node (ref "X1") (pin "1") (pinfunction "1_1") (pintype "passive"))
    )
    (net (code "65") (name "/PB15") (class "Default")
      (node (ref "LCD1") (pin "29") (pinfunction "XPT_MOSI_29") (pintype "passive"))
      (node (ref "U1") (pin "28") (pinfunction "PB15/SPI2_MOSI/TIM1_CH3N_28") (pintype "passive"))
      (node (ref "X2") (pin "16") (pinfunction "16_16") (pintype "passive"))
    )
    (net (code "66") (name "/R2OUT") (class "Default")
      (node (ref "JP6") (pin "1") (pinfunction "1_1") (pintype "passive"))
      (node (ref "U3") (pin "9") (pinfunction "R2OUT_9") (pintype "passive"))
    )
    (net (code "67") (name "/S1") (class "Default")
      (node (ref "Q1") (pin "12") (pinfunction "L_1_12") (pintype "passive"))
      (node (ref "V3") (pin "C") (pinfunction "C_C") (pintype "passive"))
    )
    (net (code "68") (name "/S2") (class "Default")
      (node (ref "Q1") (pin "9") (pinfunction "L_2_9") (pintype "passive"))
      (node (ref "V4") (pin "C") (pinfunction "C_C") (pintype "passive"))
    )
    (net (code "69") (name "/S3") (class "Default")
      (node (ref "Q1") (pin "8") (pinfunction "L_3_8") (pintype "passive"))
      (node (ref "V5") (pin "C") (pinfunction "C_C") (pintype "passive"))
    )
    (net (code "70") (name "/S4") (class "Default")
      (node (ref "Q1") (pin "6") (pinfunction "L_4_6") (pintype "passive"))
      (node (ref "V6") (pin "C") (pinfunction "C_C") (pintype "passive"))
    )
    (net (code "71") (name "/SP_CS") (class "Default")
      (node (ref "JP13") (pin "1") (pinfunction "1_1") (pintype "passive"))
      (node (ref "R8") (pin "1") (pinfunction "1_1") (pintype "passive"))
      (node (ref "U7") (pin "1") (pinfunction "~{CS}_1") (pintype "passive"))
    )
    (net (code "72") (name "/SP_MISO") (class "Default")
      (node (ref "JP13") (pin "3") (pinfunction "3_3") (pintype "passive"))
      (node (ref "U7") (pin "2") (pinfunction "DO_2") (pintype "passive"))
    )
    (net (code "73") (name "/SP_MOSI") (class "Default")
      (node (ref "JP13") (pin "4") (pinfunction "4_4") (pintype "passive"))
      (node (ref "U7") (pin "5") (pinfunction "DI_5") (pintype "passive"))
    )
    (net (code "74") (name "/SP_SCK") (class "Default")
      (node (ref "JP13") (pin "2") (pinfunction "2_2") (pintype "passive"))
      (node (ref "U7") (pin "6") (pinfunction "CLK_6") (pintype "passive"))
    )
    (net (code "75") (name "/T2IN") (class "Default")
      (node (ref "JP6") (pin "2") (pinfunction "2_2") (pintype "passive"))
      (node (ref "U3") (pin "10") (pinfunction "T2IN_10") (pintype "passive"))
    )
    (net (code "76") (name "/VBAT") (class "Default")
      (node (ref "C8") (pin "2") (pinfunction "2_2") (pintype "passive"))
      (node (ref "D1") (pin "2") (pinfunction "K_2") (pintype "passive"))
      (node (ref "D2") (pin "2") (pinfunction "K_2") (pintype "passive"))
      (node (ref "U1") (pin "1") (pinfunction "VBAT_1") (pintype "passive"))
    )
    (net (code "77") (name "3V3") (class "Default")
      (node (ref "BEEP1") (pin "1") (pinfunction "+_1") (pintype "passive"))
      (node (ref "C11") (pin "1") (pinfunction "1_1") (pintype "passive"))
      (node (ref "C12") (pin "1") (pinfunction "1_1") (pintype "passive"))
      (node (ref "C13") (pin "2") (pinfunction "2_2") (pintype "passive"))
      (node (ref "C16") (pin "1") (pinfunction "1_1") (pintype "passive"))
      (node (ref "C19") (pin "1") (pinfunction "1_1") (pintype "passive"))
      (node (ref "C20") (pin "2") (pinfunction "2_2") (pintype "passive"))
      (node (ref "C21") (pin "2") (pinfunction "2_2") (pintype "passive"))
      (node (ref "C22") (pin "1") (pinfunction "1_1") (pintype "passive"))
      (node (ref "C23") (pin "1") (pinfunction "1_1") (pintype "passive"))
      (node (ref "C24") (pin "1") (pinfunction "1_1") (pintype "passive"))
      (node (ref "C25") (pin "1") (pinfunction "1_1") (pintype "passive"))
      (node (ref "C26") (pin "2") (pinfunction "2_2") (pintype "passive"))
      (node (ref "C27") (pin "1") (pinfunction "1_1") (pintype "passive"))
      (node (ref "C28") (pin "1") (pinfunction "1_1") (pintype "passive"))
      (node (ref "D2") (pin "1") (pinfunction "A_1") (pintype "passive"))
      (node (ref "JP1") (pin "1") (pinfunction "1_1") (pintype "passive"))
      (node (ref "JP2") (pin "1") (pinfunction "1_1") (pintype "passive"))
      (node (ref "LCD1") (pin "2") (pinfunction "3V3_2") (pintype "passive"))
      (node (ref "N1") (pin "2") (pinfunction "VOUT_2") (pintype "passive"))
      (node (ref "N1") (pin "4") (pinfunction "VOUT_4") (pintype "passive"))
      (node (ref "R1") (pin "2") (pinfunction "2_2") (pintype "passive"))
      (node (ref "R11") (pin "2") (pinfunction "2_2") (pintype "passive"))
      (node (ref "R12") (pin "1") (pinfunction "1_1") (pintype "passive"))
      (node (ref "R13") (pin "1") (pinfunction "1_1") (pintype "passive"))
      (node (ref "R14") (pin "1") (pinfunction "1_1") (pintype "passive"))
      (node (ref "R15") (pin "1") (pinfunction "1_1") (pintype "passive"))
      (node (ref "R17") (pin "2") (pinfunction "2_2") (pintype "passive"))
      (node (ref "R18") (pin "2") (pinfunction "2_2") (pintype "passive"))
      (node (ref "R19") (pin "2") (pinfunction "2_2") (pintype "passive"))
      (node (ref "R20") (pin "2") (pinfunction "2_2") (pintype "passive"))
      (node (ref "R21") (pin "1") (pinfunction "1_1") (pintype "passive"))
      (node (ref "R22") (pin "1") (pinfunction "1_1") (pintype "passive"))
      (node (ref "R23") (pin "2") (pinfunction "2_2") (pintype "passive"))
      (node (ref "R24") (pin "2") (pinfunction "2_2") (pintype "passive"))
      (node (ref "R25") (pin "2") (pinfunction "2_2") (pintype "passive"))
      (node (ref "R26") (pin "2") (pinfunction "2_2") (pintype "passive"))
      (node (ref "R4") (pin "1") (pinfunction "1_1") (pintype "passive"))
      (node (ref "R5") (pin "2") (pinfunction "2_2") (pintype "passive"))
      (node (ref "R8") (pin "2") (pinfunction "2_2") (pintype "passive"))
      (node (ref "R9") (pin "1") (pinfunction "1_1") (pintype "passive"))
      (node (ref "U1") (pin "24") (pinfunction "VDD_1_24") (pintype "passive"))
      (node (ref "U1") (pin "36") (pinfunction "VDD_2_36") (pintype "passive"))
      (node (ref "U1") (pin "48") (pinfunction "VDD_3_48") (pintype "passive"))
      (node (ref "U1") (pin "9") (pinfunction "VDDA_9") (pintype "passive"))
      (node (ref "U10") (pin "16") (pinfunction "VCC_16") (pintype "passive"))
      (node (ref "U2") (pin "16") (pinfunction "VCC_16") (pintype "passive"))
      (node (ref "U2") (pin "4") (pinfunction "V3_4") (pintype "passive"))
      (node (ref "U3") (pin "16") (pinfunction "VCC_16") (pintype "passive"))
      (node (ref "U4") (pin "8") (pinfunction "VCC_8") (pintype "passive"))
      (node (ref "U5") (pin "3") (pinfunction "VCC_3") (pintype "passive"))
      (node (ref "U6") (pin "8") (pinfunction "VCC_8") (pintype "passive"))
      (node (ref "U7") (pin "3") (pinfunction "~{WP}_3") (pintype "passive"))
      (node (ref "U7") (pin "7") (pinfunction "~{HOLD}_7") (pintype "passive"))
      (node (ref "U7") (pin "8") (pinfunction "VCC_8") (pintype "passive"))
      (node (ref "U8") (pin "2") (pinfunction "VCC_2") (pintype "passive"))
      (node (ref "U9") (pin "16") (pinfunction "VCC_16") (pintype "passive"))
      (node (ref "X5") (pin "1") (pinfunction "1_1") (pintype "passive"))
      (node (ref "X5") (pin "2") (pinfunction "2_2") (pintype "passive"))
      (node (ref "X5") (pin "3") (pinfunction "3_3") (pintype "passive"))
      (node (ref "Z1") (pin "1") (pinfunction "1_1") (pintype "passive"))
      (node (ref "Z1") (pin "2") (pinfunction "2_2") (pintype "passive"))
    )
    (net (code "78") (name "5V") (class "Default")
      (node (ref "C10") (pin "1") (pinfunction "1_1") (pintype "passive"))
      (node (ref "C9") (pin "1") (pinfunction "1_1") (pintype "passive"))
      (node (ref "N1") (pin "3") (pinfunction "VIN_3") (pintype "passive"))
      (node (ref "S1") (pin "3") (pintype "passive"))
      (node (ref "X3") (pin "1") (pinfunction "1_1") (pintype "passive"))
      (node (ref "X3") (pin "2") (pinfunction "2_2") (pintype "passive"))
      (node (ref "X3") (pin "3") (pinfunction "3_3") (pintype "passive"))
    )
    (net (code "79") (name "GND") (class "Default")
      (node (ref "B1") (pin "2") (pinfunction "-_2") (pintype "passive"))
      (node (ref "C1") (pin "1") (pinfunction "1_1") (pintype "passive"))
      (node (ref "C10") (pin "2") (pinfunction "2_2") (pintype "passive"))
      (node (ref "C11") (pin "2") (pinfunction "2_2") (pintype "passive"))
      (node (ref "C12") (pin "2") (pinfunction "2_2") (pintype "passive"))
      (node (ref "C13") (pin "1") (pinfunction "1_1") (pintype "passive"))
      (node (ref "C16") (pin "2") (pinfunction "2_2") (pintype "passive"))
      (node (ref "C17") (pin "2") (pinfunction "2_2") (pintype "passive"))
      (node (ref "C18") (pin "2") (pinfunction "2_2") (pintype "passive"))
      (node (ref "C19") (pin "2") (pinfunction "2_2") (pintype "passive"))
      (node (ref "C2") (pin "2") (pinfunction "2_2") (pintype "passive"))
      (node (ref "C20") (pin "1") (pinfunction "1_1") (pintype "passive"))
      (node (ref "C21") (pin "1") (pinfunction "1_1") (pintype "passive"))
      (node (ref "C22") (pin "2") (pinfunction "2_2") (pintype "passive"))
      (node (ref "C23") (pin "2") (pinfunction "2_2") (pintype "passive"))
      (node (ref "C24") (pin "2") (pinfunction "2_2") (pintype "passive"))
      (node (ref "C25") (pin "2") (pinfunction "2_2") (pintype "passive"))
      (node (ref "C26") (pin "1") (pinfunction "1_1") (pintype "passive"))
      (node (ref "C27") (pin "2") (pinfunction "2_2") (pintype "passive"))
      (node (ref "C28") (pin "2") (pinfunction "2_2") (pintype "passive"))
      (node (ref "C3") (pin "2") (pinfunction "2_2") (pintype "passive"))
      (node (ref "C4") (pin "2") (pinfunction "2_2") (pintype "passive"))
      (node (ref "C5") (pin "2") (pinfunction "2_2") (pintype "passive"))
      (node (ref "C6") (pin "1") (pinfunction "1_1") (pintype "passive"))
      (node (ref "C7") (pin "1") (pinfunction "1_1") (pintype "passive"))
      (node (ref "C8") (pin "1") (pinfunction "1_1") (pintype "passive"))
      (node (ref "C9") (pin "2") (pinfunction "2_2") (pintype "passive"))
      (node (ref "DB1") (pin "5") (pinfunction "5_5") (pintype "passive"))
      (node (ref "H1") (pin "2") (pinfunction "K_2") (pintype "passive"))
      (node (ref "JP1") (pin "3") (pinfunction "3_3") (pintype "passive"))
      (node (ref "JP2") (pin "3") (pinfunction "3_3") (pintype "passive"))
      (node (ref "KEY1") (pin "1") (pinfunction "1_1") (pintype "passive"))
      (node (ref "KEY1") (pin "3") (pinfunction "3_3") (pintype "passive"))
      (node (ref "KEY2") (pin "1") (pinfunction "1_1") (pintype "passive"))
      (node (ref "KEY2") (pin "3") (pinfunction "3_3") (pintype "passive"))
      (node (ref "KEY3") (pin "1") (pinfunction "1_1") (pintype "passive"))
      (node (ref "KEY3") (pin "3") (pinfunction "3_3") (pintype "passive"))
      (node (ref "KEY4") (pin "1") (pinfunction "1_1") (pintype "passive"))
      (node (ref "KEY4") (pin "3") (pinfunction "3_3") (pintype "passive"))
      (node (ref "LCD1") (pin "1") (pinfunction "GND_1") (pintype "passive"))
      (node (ref "N1") (pin "1") (pinfunction "GND_1") (pintype "passive"))
      (node (ref "R16") (pin "2") (pinfunction "2_2") (pintype "passive"))
      (node (ref "R6") (pin "1") (pinfunction "1_1") (pintype "passive"))
      (node (ref "U1") (pin "23") (pinfunction "VSS_1_23") (pintype "passive"))
      (node (ref "U1") (pin "35") (pinfunction "VSS_2_35") (pintype "passive"))
      (node (ref "U1") (pin "47") (pinfunction "VSS_3_47") (pintype "passive"))
      (node (ref "U1") (pin "8") (pinfunction "VSSA_8") (pintype "passive"))
      (node (ref "U10") (pin "13") (pinfunction "~{EN}_13") (pintype "passive"))
      (node (ref "U10") (pin "8") (pinfunction "GND_8") (pintype "passive"))
      (node (ref "U2") (pin "1") (pinfunction "GND_1") (pintype "passive"))
      (node (ref "U3") (pin "15") (pinfunction "GND_15") (pintype "passive"))
      (node (ref "U4") (pin "5") (pinfunction "GND_5") (pintype "passive"))
      (node (ref "U5") (pin "2") (pinfunction "GND_2") (pintype "passive"))
      (node (ref "U5") (pin "8") (pinfunction "Rs_8") (pintype "passive"))
      (node (ref "U6") (pin "1") (pinfunction "A0_1") (pintype "passive"))
      (node (ref "U6") (pin "2") (pinfunction "A1_2") (pintype "passive"))
      (node (ref "U6") (pin "3") (pinfunction "A2_3") (pintype "passive"))
      (node (ref "U6") (pin "4") (pinfunction "GND_4") (pintype "passive"))
      (node (ref "U6") (pin "7") (pinfunction "WP_7") (pintype "passive"))
      (node (ref "U7") (pin "4") (pinfunction "GND_4") (pintype "passive"))
      (node (ref "U8") (pin "1") (pinfunction "GND_1") (pintype "passive"))
      (node (ref "U9") (pin "13") (pinfunction "~{EN}_13") (pintype "passive"))
      (node (ref "U9") (pin "8") (pinfunction "GND_8") (pintype "passive"))
      (node (ref "USB1") (pin "5") (pinfunction "GND_5") (pintype "passive"))
      (node (ref "USB2") (pin "5") (pinfunction "GND_5") (pintype "passive"))
      (node (ref "V1") (pin "E") (pinfunction "E_E") (pintype "passive"))
      (node (ref "V2") (pin "E") (pinfunction "E_E") (pintype "passive"))
      (node (ref "X4") (pin "1") (pinfunction "1_1") (pintype "passive"))
      (node (ref "X4") (pin "2") (pinfunction "2_2") (pintype "passive"))
      (node (ref "X4") (pin "3") (pinfunction "3_3") (pintype "passive"))
      (node (ref "X6") (pin "1") (pinfunction "1_1") (pintype "passive"))
      (node (ref "X6") (pin "2") (pinfunction "2_2") (pintype "passive"))
      (node (ref "X6") (pin "3") (pinfunction "3_3") (pintype "passive"))
      (node (ref "Z1") (pin "10") (pinfunction "10_10") (pintype "passive"))
      (node (ref "Z1") (pin "12") (pinfunction "12_12") (pintype "passive"))
      (node (ref "Z1") (pin "14") (pinfunction "14_14") (pintype "passive"))
      (node (ref "Z1") (pin "16") (pinfunction "16_16") (pintype "passive"))
      (node (ref "Z1") (pin "18") (pinfunction "18_18") (pintype "passive"))
      (node (ref "Z1") (pin "20") (pinfunction "20_20") (pintype "passive"))
      (node (ref "Z1") (pin "4") (pinfunction "4_4") (pintype "passive"))
      (node (ref "Z1") (pin "6") (pinfunction "6_6") (pintype "passive"))
      (node (ref "Z1") (pin "8") (pinfunction "8_8") (pintype "passive"))
    )
    (net (code "80") (name "Net-(B1-+)") (class "Default")
      (node (ref "B1") (pin "1") (pinfunction "+_1") (pintype "passive"))
      (node (ref "D1") (pin "1") (pinfunction "A_1") (pintype "passive"))
    )
    (net (code "81") (name "Net-(BEEP1--)") (class "Default")
      (node (ref "BEEP1") (pin "2") (pinfunction "-_2") (pintype "passive"))
      (node (ref "V2") (pin "C") (pinfunction "C_C") (pintype "passive"))
    )
    (net (code "82") (name "Net-(H1-A)") (class "Default")
      (node (ref "H1") (pin "1") (pinfunction "A_1") (pintype "passive"))
      (node (ref "R9") (pin "2") (pinfunction "2_2") (pintype "passive"))
    )
    (net (code "83") (name "Net-(H2-A)") (class "Default")
      (node (ref "H2") (pin "1") (pinfunction "A_1") (pintype "passive"))
      (node (ref "R12") (pin "2") (pinfunction "2_2") (pintype "passive"))
    )
    (net (code "84") (name "Net-(H2-K)") (class "Default")
      (node (ref "H2") (pin "2") (pinfunction "K_2") (pintype "passive"))
      (node (ref "JP16") (pin "1") (pinfunction "1_1") (pintype "passive"))
    )
    (net (code "85") (name "Net-(H3-A)") (class "Default")
      (node (ref "H3") (pin "1") (pinfunction "A_1") (pintype "passive"))
      (node (ref "R13") (pin "2") (pinfunction "2_2") (pintype "passive"))
    )
    (net (code "86") (name "Net-(H3-K)") (class "Default")
      (node (ref "H3") (pin "2") (pinfunction "K_2") (pintype "passive"))
      (node (ref "JP16") (pin "2") (pinfunction "2_2") (pintype "passive"))
    )
    (net (code "87") (name "Net-(H4-A)") (class "Default")
      (node (ref "H4") (pin "1") (pinfunction "A_1") (pintype "passive"))
      (node (ref "R14") (pin "2") (pinfunction "2_2") (pintype "passive"))
    )
    (net (code "88") (name "Net-(H4-K)") (class "Default")
      (node (ref "H4") (pin "2") (pinfunction "K_2") (pintype "passive"))
      (node (ref "JP16") (pin "3") (pinfunction "3_3") (pintype "passive"))
    )
    (net (code "89") (name "Net-(H5-A)") (class "Default")
      (node (ref "H5") (pin "1") (pinfunction "A_1") (pintype "passive"))
      (node (ref "R15") (pin "2") (pinfunction "2_2") (pintype "passive"))
    )
    (net (code "90") (name "Net-(H5-K)") (class "Default")
      (node (ref "H5") (pin "2") (pinfunction "K_2") (pintype "passive"))
      (node (ref "JP16") (pin "4") (pinfunction "4_4") (pintype "passive"))
    )
    (net (code "91") (name "Net-(JP1-Pad2)") (class "Default")
      (node (ref "JP1") (pin "2") (pinfunction "2_2") (pintype "passive"))
      (node (ref "R2") (pin "2") (pinfunction "2_2") (pintype "passive"))
    )
    (net (code "92") (name "Net-(JP2-Pad2)") (class "Default")
      (node (ref "JP2") (pin "2") (pinfunction "2_2") (pintype "passive"))
      (node (ref "R3") (pin "2") (pinfunction "2_2") (pintype "passive"))
    )
    (net (code "93") (name "Net-(JP15-Pad1)") (class "Default")
      (node (ref "JP15") (pin "1") (pinfunction "1_1") (pintype "passive"))
      (node (ref "R7") (pin "1") (pinfunction "1_1") (pintype "passive"))
    )
    (net (code "94") (name "Net-(R6-Pad2)") (class "Default")
      (node (ref "R6") (pin "2") (pinfunction "2_2") (pintype "passive"))
      (node (ref "R7") (pin "2") (pinfunction "2_2") (pintype "passive"))
      (node (ref "V2") (pin "B") (pinfunction "B_B") (pintype "passive"))
    )
    (net (code "95") (name "Net-(R10-Pad2)") (class "Default")
      (node (ref "R10") (pin "2") (pinfunction "2_2") (pintype "passive"))
      (node (ref "V1") (pin "B") (pinfunction "B_B") (pintype "passive"))
    )
    (net (code "96") (name "Net-(R23-Pad1)") (class "Default")
      (node (ref "R23") (pin "1") (pinfunction "1_1") (pintype "passive"))
      (node (ref "V3") (pin "E") (pinfunction "E_E") (pintype "passive"))
    )
    (net (code "97") (name "Net-(R24-Pad1)") (class "Default")
      (node (ref "R24") (pin "1") (pinfunction "1_1") (pintype "passive"))
      (node (ref "V4") (pin "E") (pinfunction "E_E") (pintype "passive"))
    )
    (net (code "98") (name "Net-(R25-Pad1)") (class "Default")
      (node (ref "R25") (pin "1") (pinfunction "1_1") (pintype "passive"))
      (node (ref "V5") (pin "E") (pinfunction "E_E") (pintype "passive"))
    )
    (net (code "99") (name "Net-(R26-Pad1)") (class "Default")
      (node (ref "R26") (pin "1") (pinfunction "1_1") (pintype "passive"))
      (node (ref "V6") (pin "E") (pinfunction "E_E") (pintype "passive"))
    )
    (net (code "100") (name "Net-(R27-Pad2)") (class "Default")
      (node (ref "R27") (pin "2") (pintype "passive"))
      (node (ref "V3") (pin "B") (pinfunction "B_B") (pintype "passive"))
    )
    (net (code "101") (name "Net-(R28-Pad2)") (class "Default")
      (node (ref "R28") (pin "2") (pintype "passive"))
      (node (ref "V4") (pin "B") (pinfunction "B_B") (pintype "passive"))
    )
    (net (code "102") (name "Net-(R29-Pad2)") (class "Default")
      (node (ref "R29") (pin "2") (pintype "passive"))
      (node (ref "V5") (pin "B") (pinfunction "B_B") (pintype "passive"))
    )
    (net (code "103") (name "Net-(R30-Pad2)") (class "Default")
      (node (ref "R30") (pin "2") (pintype "passive"))
      (node (ref "V6") (pin "B") (pinfunction "B_B") (pintype "passive"))
    )
    (net (code "104") (name "Net-(U2-UD+)") (class "Default")
      (node (ref "U2") (pin "5") (pinfunction "UD+_5") (pintype "passive"))
      (node (ref "USB1") (pin "3") (pinfunction "D+_3") (pintype "passive"))
    )
    (net (code "105") (name "Net-(U2-UD-)") (class "Default")
      (node (ref "U2") (pin "6") (pinfunction "UD-_6") (pintype "passive"))
      (node (ref "USB1") (pin "2") (pinfunction "D-_2") (pintype "passive"))
    )
    (net (code "106") (name "Net-(U2-~{RTS})") (class "Default")
      (node (ref "R10") (pin "1") (pinfunction "1_1") (pintype "passive"))
      (node (ref "U2") (pin "14") (pinfunction "~{RTS}_14") (pintype "passive"))
    )
    (net (code "107") (name "Net-(U3-C1+)") (class "Default")
      (node (ref "C14") (pin "2") (pinfunction "2_2") (pintype "passive"))
      (node (ref "U3") (pin "1") (pinfunction "C1+_1") (pintype "passive"))
    )
    (net (code "108") (name "Net-(U3-C1-)") (class "Default")
      (node (ref "C14") (pin "1") (pinfunction "1_1") (pintype "passive"))
      (node (ref "U3") (pin "3") (pinfunction "C1-_3") (pintype "passive"))
    )
    (net (code "109") (name "Net-(U3-C2+)") (class "Default")
      (node (ref "C15") (pin "2") (pinfunction "2_2") (pintype "passive"))
      (node (ref "U3") (pin "4") (pinfunction "C2+_4") (pintype "passive"))
    )
    (net (code "110") (name "Net-(U3-C2-)") (class "Default")
      (node (ref "C15") (pin "1") (pinfunction "1_1") (pintype "passive"))
      (node (ref "U3") (pin "5") (pinfunction "C2-_5") (pintype "passive"))
    )
    (net (code "111") (name "Net-(U3-R2IN)") (class "Default")
      (node (ref "DB1") (pin "3") (pinfunction "3_3") (pintype "passive"))
      (node (ref "U3") (pin "8") (pinfunction "R2IN_8") (pintype "passive"))
    )
    (net (code "112") (name "Net-(U3-T2OUT)") (class "Default")
      (node (ref "DB1") (pin "2") (pinfunction "2_2") (pintype "passive"))
      (node (ref "U3") (pin "7") (pinfunction "T2OUT_7") (pintype "passive"))
    )
    (net (code "113") (name "Net-(U3-V+)") (class "Default")
      (node (ref "C18") (pin "1") (pinfunction "1_1") (pintype "passive"))
      (node (ref "U3") (pin "2") (pinfunction "V+_2") (pintype "passive"))
    )
    (net (code "114") (name "Net-(U3-V-)") (class "Default")
      (node (ref "C17") (pin "1") (pinfunction "1_1") (pintype "passive"))
      (node (ref "U3") (pin "6") (pinfunction "V-_6") (pintype "passive"))
    )
    (net (code "115") (name "Net-(U4-A)") (class "Default")
      (node (ref "R17") (pin "1") (pinfunction "1_1") (pintype "passive"))
      (node (ref "U4") (pin "6") (pinfunction "A_6") (pintype "passive"))
      (node (ref "X7") (pin "2") (pinfunction "2_2") (pintype "passive"))
    )
    (net (code "116") (name "Net-(U4-B)") (class "Default")
      (node (ref "R16") (pin "1") (pinfunction "1_1") (pintype "passive"))
      (node (ref "U4") (pin "7") (pinfunction "B_7") (pintype "passive"))
      (node (ref "X7") (pin "1") (pinfunction "1_1") (pintype "passive"))
    )
    (net (code "117") (name "Net-(U4-DE)") (class "Default")
      (node (ref "JP8") (pin "1") (pinfunction "1_1") (pintype "passive"))
      (node (ref "U4") (pin "2") (pinfunction "~{RE}_2") (pintype "passive"))
      (node (ref "U4") (pin "3") (pinfunction "DE_3") (pintype "passive"))
    )
    (net (code "118") (name "Net-(U4-DI)") (class "Default")
      (node (ref "JP8") (pin "2") (pinfunction "2_2") (pintype "passive"))
      (node (ref "U4") (pin "4") (pinfunction "DI_4") (pintype "passive"))
    )
    (net (code "119") (name "Net-(U4-RO)") (class "Default")
      (node (ref "JP8") (pin "3") (pinfunction "3_3") (pintype "passive"))
      (node (ref "U4") (pin "1") (pinfunction "RO_1") (pintype "passive"))
    )
    (net (code "120") (name "Net-(U5-CANH)") (class "Default")
      (node (ref "U5") (pin "7") (pinfunction "CANH_7") (pintype "passive"))
      (node (ref "X8") (pin "1") (pinfunction "1_1") (pintype "passive"))
    )
    (net (code "121") (name "Net-(U5-CANL)") (class "Default")
      (node (ref "U5") (pin "6") (pinfunction "CANL_6") (pintype "passive"))
      (node (ref "X8") (pin "2") (pinfunction "2_2") (pintype "passive"))
    )
    (net (code "122") (name "Net-(U5-RXD)") (class "Default")
      (node (ref "JP10") (pin "2") (pinfunction "2_2") (pintype "passive"))
      (node (ref "U5") (pin "4") (pinfunction "RXD_4") (pintype "passive"))
    )
    (net (code "123") (name "Net-(U5-TXD)") (class "Default")
      (node (ref "JP10") (pin "1") (pinfunction "1_1") (pintype "passive"))
      (node (ref "U5") (pin "1") (pinfunction "TXD_1") (pintype "passive"))
    )
    (net (code "124") (name "Net-(U9-RESET)") (class "Default")
      (node (ref "R21") (pin "2") (pinfunction "2_2") (pintype "passive"))
      (node (ref "U9") (pin "10") (pinfunction "RESET_10") (pintype "passive"))
    )
    (net (code "125") (name "Net-(U10-RESET)") (class "Default")
      (node (ref "R22") (pin "2") (pinfunction "2_2") (pintype "passive"))
      (node (ref "U10") (pin "10") (pinfunction "RESET_10") (pintype "passive"))
    )
    (net (code "126") (name "VUSB") (class "Default")
      (node (ref "S1") (pin "2") (pintype "passive"))
      (node (ref "USB1") (pin "1") (pinfunction "VCC_1") (pintype "passive"))
      (node (ref "USB2") (pin "1") (pinfunction "VCC_1") (pintype "passive"))
    )
    (net (code "127") (name "unconnected-(DB1-Pad1)") (class "Default")
      (node (ref "DB1") (pin "1") (pinfunction "1_1") (pintype "passive"))
    )
    (net (code "128") (name "unconnected-(DB1-Pad4)") (class "Default")
      (node (ref "DB1") (pin "4") (pinfunction "4_4") (pintype "passive"))
    )
    (net (code "129") (name "unconnected-(DB1-Pad6)") (class "Default")
      (node (ref "DB1") (pin "6") (pinfunction "6_6") (pintype "passive"))
    )
    (net (code "130") (name "unconnected-(DB1-Pad7)") (class "Default")
      (node (ref "DB1") (pin "7") (pinfunction "7_7") (pintype "passive"))
    )
    (net (code "131") (name "unconnected-(DB1-Pad8)") (class "Default")
      (node (ref "DB1") (pin "8") (pinfunction "8_8") (pintype "passive"))
    )
    (net (code "132") (name "unconnected-(DB1-Pad9)") (class "Default")
      (node (ref "DB1") (pin "9") (pinfunction "9_9") (pintype "passive"))
    )
    (net (code "133") (name "unconnected-(LCD1-DB0-Pad10)") (class "Default")
      (node (ref "LCD1") (pin "10") (pinfunction "DB0_10") (pintype "passive"))
    )
    (net (code "134") (name "unconnected-(LCD1-DB1-Pad11)") (class "Default")
      (node (ref "LCD1") (pin "11") (pinfunction "DB1_11") (pintype "passive"))
    )
    (net (code "135") (name "unconnected-(LCD1-DB2-Pad12)") (class "Default")
      (node (ref "LCD1") (pin "12") (pinfunction "DB2_12") (pintype "passive"))
    )
    (net (code "136") (name "unconnected-(LCD1-DB3-Pad13)") (class "Default")
      (node (ref "LCD1") (pin "13") (pinfunction "DB3_13") (pintype "passive"))
    )
    (net (code "137") (name "unconnected-(LCD1-DB4-Pad14)") (class "Default")
      (node (ref "LCD1") (pin "14") (pinfunction "DB4_14") (pintype "passive"))
    )
    (net (code "138") (name "unconnected-(LCD1-DB5-Pad15)") (class "Default")
      (node (ref "LCD1") (pin "15") (pinfunction "DB5_15") (pintype "passive"))
    )
    (net (code "139") (name "unconnected-(LCD1-DB6-Pad16)") (class "Default")
      (node (ref "LCD1") (pin "16") (pinfunction "DB6_16") (pintype "passive"))
    )
    (net (code "140") (name "unconnected-(LCD1-DB7-Pad17)") (class "Default")
      (node (ref "LCD1") (pin "17") (pinfunction "DB7_17") (pintype "passive"))
    )
    (net (code "141") (name "unconnected-(LCD1-LCD_MISO-Pad8)") (class "Default")
      (node (ref "LCD1") (pin "8") (pinfunction "LCD_MISO_8") (pintype "passive"))
    )
    (net (code "142") (name "unconnected-(LCD1-LCD_MOSI-Pad7)") (class "Default")
      (node (ref "LCD1") (pin "7") (pinfunction "LCD_MOSI_7") (pintype "passive"))
    )
    (net (code "143") (name "unconnected-(LCD1-XPT_BUSY-Pad30)") (class "Default")
      (node (ref "LCD1") (pin "30") (pinfunction "XPT_BUSY_30") (pintype "passive"))
    )
    (net (code "144") (name "unconnected-(S1-Pad1)") (class "Default")
      (node (ref "S1") (pin "1") (pintype "passive"))
    )
    (net (code "145") (name "unconnected-(S1-Pad4)") (class "Default")
      (node (ref "S1") (pin "4") (pintype "passive"))
    )
    (net (code "146") (name "unconnected-(S1-Pad5)") (class "Default")
      (node (ref "S1") (pin "5") (pintype "passive"))
    )
    (net (code "147") (name "unconnected-(S1-Pad6)") (class "Default")
      (node (ref "S1") (pin "6") (pintype "passive"))
    )
    (net (code "148") (name "unconnected-(U2-R232-Pad15)") (class "Default")
      (node (ref "U2") (pin "15") (pinfunction "R232_15") (pintype "passive"))
    )
    (net (code "149") (name "unconnected-(U2-~{CTS}-Pad9)") (class "Default")
      (node (ref "U2") (pin "9") (pinfunction "~{CTS}_9") (pintype "passive"))
    )
    (net (code "150") (name "unconnected-(U2-~{DCD}-Pad12)") (class "Default")
      (node (ref "U2") (pin "12") (pinfunction "~{DCD}_12") (pintype "passive"))
    )
    (net (code "151") (name "unconnected-(U2-~{DSR}-Pad10)") (class "Default")
      (node (ref "U2") (pin "10") (pinfunction "~{DSR}_10") (pintype "passive"))
    )
    (net (code "152") (name "unconnected-(U2-~{RI}-Pad11)") (class "Default")
      (node (ref "U2") (pin "11") (pinfunction "~{RI}_11") (pintype "passive"))
    )
    (net (code "153") (name "unconnected-(U3-R1IN-Pad13)") (class "Default")
      (node (ref "U3") (pin "13") (pinfunction "R1IN_13") (pintype "passive"))
    )
    (net (code "154") (name "unconnected-(U3-R1OUT-Pad12)") (class "Default")
      (node (ref "U3") (pin "12") (pinfunction "R1OUT_12") (pintype "passive"))
    )
    (net (code "155") (name "unconnected-(U3-T1IN-Pad11)") (class "Default")
      (node (ref "U3") (pin "11") (pinfunction "T1IN_11") (pintype "passive"))
    )
    (net (code "156") (name "unconnected-(U3-T1OUT-Pad14)") (class "Default")
      (node (ref "U3") (pin "14") (pinfunction "T1OUT_14") (pintype "passive"))
    )
    (net (code "157") (name "unconnected-(U5-Vref-Pad5)") (class "Default")
      (node (ref "U5") (pin "5") (pinfunction "Vref_5") (pintype "passive"))
    )
    (net (code "158") (name "unconnected-(U10-QE-Pad4)") (class "Default")
      (node (ref "U10") (pin "4") (pinfunction "QE_4") (pintype "passive"))
    )
    (net (code "159") (name "unconnected-(U10-QF-Pad5)") (class "Default")
      (node (ref "U10") (pin "5") (pinfunction "QF_5") (pintype "passive"))
    )
    (net (code "160") (name "unconnected-(U10-QG-Pad6)") (class "Default")
      (node (ref "U10") (pin "6") (pinfunction "QG_6") (pintype "passive"))
    )
    (net (code "161") (name "unconnected-(U10-QH-Pad7)") (class "Default")
      (node (ref "U10") (pin "7") (pinfunction "QH_7") (pintype "passive"))
    )
    (net (code "162") (name "unconnected-(U10-SQH-Pad9)") (class "Default")
      (node (ref "U10") (pin "9") (pinfunction "SQH_9") (pintype "passive"))
    )
    (net (code "163") (name "unconnected-(USB1-NC-Pad4)") (class "Default")
      (node (ref "USB1") (pin "4") (pinfunction "NC_4") (pintype "passive"))
    )
    (net (code "164") (name "unconnected-(USB2-NC-Pad4)") (class "Default")
      (node (ref "USB2") (pin "4") (pinfunction "NC_4") (pintype "passive"))
    )
    (net (code "165") (name "unconnected-(Z1-Pad11)") (class "Default")
      (node (ref "Z1") (pin "11") (pinfunction "11_11") (pintype "passive+no_connect"))
    )
    (net (code "166") (name "unconnected-(Z1-Pad17)") (class "Default")
      (node (ref "Z1") (pin "17") (pinfunction "17_17") (pintype "passive+no_connect"))
    )
    (net (code "167") (name "unconnected-(Z1-Pad19)") (class "Default")
      (node (ref "Z1") (pin "19") (pinfunction "19_19") (pintype "passive+no_connect"))
    )
  )
)
